# TE2015_Expansion_Board.net
KiCad netlist of a schematic drawn in EAGLE
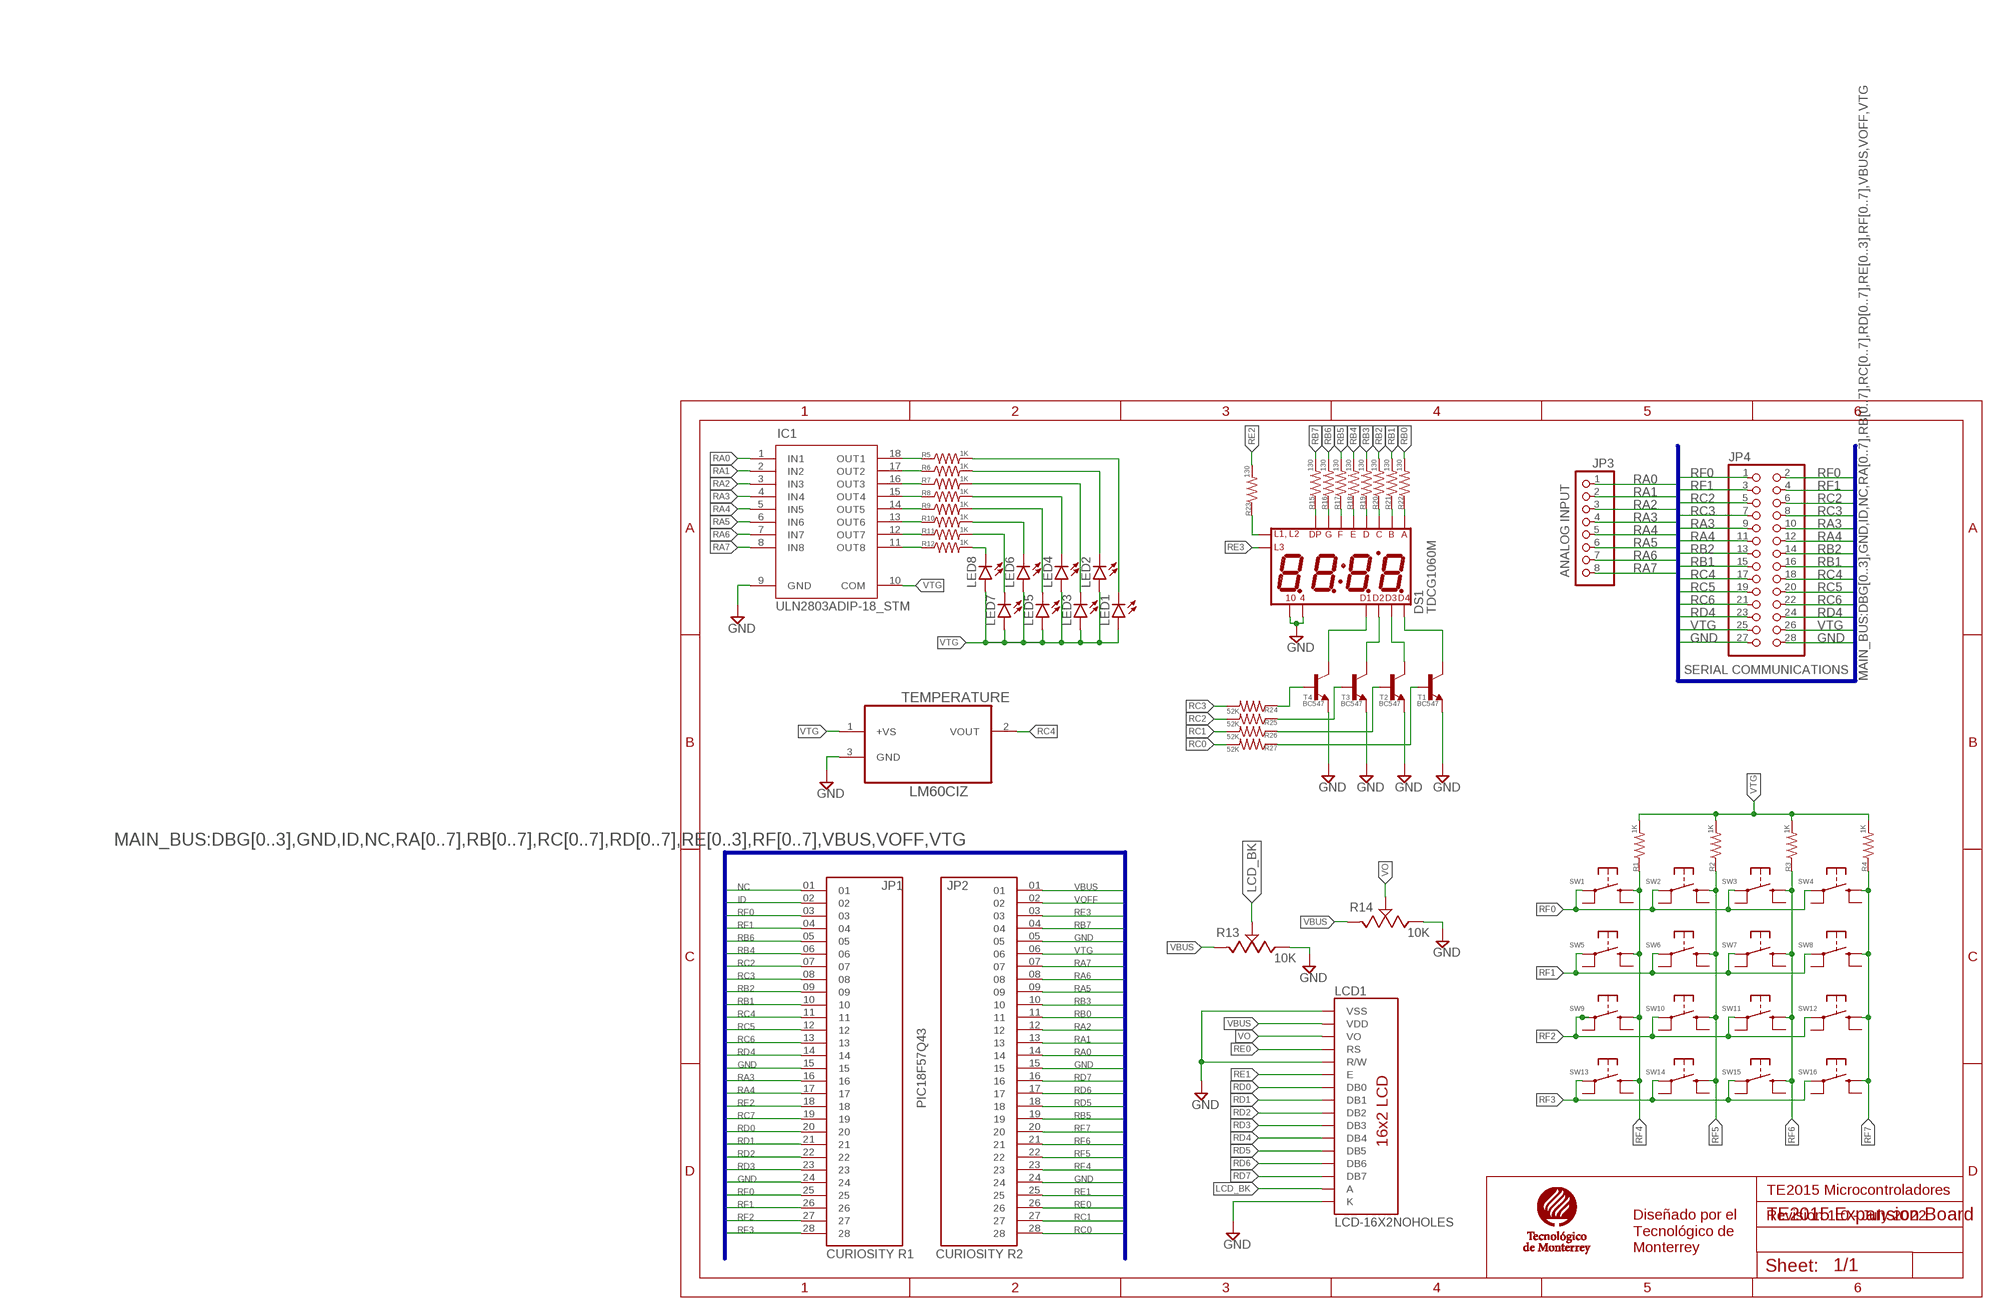
[diagram p0: schematic, sheet 1]

(export (version "E")
  (design (tool "Eeschema 10.0.6"))
  (components
    (comp (ref "DS1")
      (value "TDCG1060M")
      (footprint "eagle-import:DISPLAY_TDCG1060M")
      (fields (field (name "DIGI-KEY_PART_NUMBER") "TDCG1060M-ND") (field (name "MF") "Vishay"))
      (libsource (lib "eagle-import") (part "TDCG1060M"))
    )
    (comp (ref "IC1")
      (value "ULN2803ADIP-18_STM")
      (footprint "eagle-import:DIP-18_STM")
      (fields
        (field (name "MANUFACTURER_PART_NUMBER") "ULN2803A")
        (field (name "COPYRIGHT") "Copyright (C) 2022 Ultra Librarian. All rights reserved.")
      )
      (libsource (lib "eagle-import") (part "ULN2803ADIP-18_STM"))
    )
    (comp (ref "JP1")
      (value "CURIOSITY R1")
      (footprint "eagle-import:SAMTEC_SS-128-T-2")
      (fields
        (field (name "DIGI-KEY_PART_NUMBER") "SAM1117-28-ND")
        (field (name "MF") "Samtec")
        (field (name "MP") "SS-128-T-2")
      )
      (libsource (lib "eagle-import") (part "SS-128-T-2"))
    )
    (comp (ref "JP2")
      (value "CURIOSITY R2")
      (footprint "eagle-import:SAMTEC_SS-128-T-2")
      (fields
        (field (name "DIGI-KEY_PART_NUMBER") "SAM1117-28-ND")
        (field (name "MF") "Samtec")
        (field (name "MP") "SS-128-T-2")
      )
      (libsource (lib "eagle-import") (part "SS-128-T-2"))
    )
    (comp (ref "JP3")
      (value "ANALOG INPUT")
      (footprint "eagle-import:1X08-BIG")
      (libsource (lib "eagle-import") (part "PINHD-1X8BIG"))
    )
    (comp (ref "JP4")
      (value "SERIAL COMMUNICATIONS")
      (footprint "eagle-import:2X14-BIG")
      (libsource (lib "eagle-import") (part "PINHD-2X14-CB"))
    )
    (comp (ref "LCD1")
      (value "LCD-16X2NOHOLES")
      (footprint "eagle-import:LCD-16X2_NOHOLESNOSILK")
      (libsource (lib "eagle-import") (part "LCD-16X2NOHOLES"))
    )
    (comp (ref "LED1")
      (value "LED3MM")
      (footprint "eagle-import:LED3MM")
      (libsource (lib "eagle-import") (part "LED3MM"))
    )
    (comp (ref "LED2")
      (value "LED3MM")
      (footprint "eagle-import:LED3MM")
      (libsource (lib "eagle-import") (part "LED3MM"))
    )
    (comp (ref "LED3")
      (value "LED3MM")
      (footprint "eagle-import:LED3MM")
      (libsource (lib "eagle-import") (part "LED3MM"))
    )
    (comp (ref "LED4")
      (value "LED3MM")
      (footprint "eagle-import:LED3MM")
      (libsource (lib "eagle-import") (part "LED3MM"))
    )
    (comp (ref "LED5")
      (value "LED3MM")
      (footprint "eagle-import:LED3MM")
      (libsource (lib "eagle-import") (part "LED3MM"))
    )
    (comp (ref "LED6")
      (value "LED3MM")
      (footprint "eagle-import:LED3MM")
      (libsource (lib "eagle-import") (part "LED3MM"))
    )
    (comp (ref "LED7")
      (value "LED3MM")
      (footprint "eagle-import:LED3MM")
      (libsource (lib "eagle-import") (part "LED3MM"))
    )
    (comp (ref "LED8")
      (value "LED3MM")
      (footprint "eagle-import:LED3MM")
      (libsource (lib "eagle-import") (part "LED3MM"))
    )
    (comp (ref "R1")
      (value "1K")
      (footprint "eagle-import:0207_10")
      (libsource (lib "eagle-import") (part "R-US"))
    )
    (comp (ref "R2")
      (value "1K")
      (footprint "eagle-import:0207_10")
      (libsource (lib "eagle-import") (part "R-US"))
    )
    (comp (ref "R3")
      (value "1K")
      (footprint "eagle-import:0207_10")
      (libsource (lib "eagle-import") (part "R-US"))
    )
    (comp (ref "R4")
      (value "1K")
      (footprint "eagle-import:0207_10")
      (libsource (lib "eagle-import") (part "R-US"))
    )
    (comp (ref "R5")
      (value "1K")
      (footprint "eagle-import:0207_10")
      (libsource (lib "eagle-import") (part "R-US"))
    )
    (comp (ref "R6")
      (value "1K")
      (footprint "eagle-import:0207_10")
      (libsource (lib "eagle-import") (part "R-US"))
    )
    (comp (ref "R7")
      (value "1K")
      (footprint "eagle-import:0207_10")
      (libsource (lib "eagle-import") (part "R-US"))
    )
    (comp (ref "R8")
      (value "1K")
      (footprint "eagle-import:0207_10")
      (libsource (lib "eagle-import") (part "R-US"))
    )
    (comp (ref "R9")
      (value "1K")
      (footprint "eagle-import:0207_10")
      (libsource (lib "eagle-import") (part "R-US"))
    )
    (comp (ref "R10")
      (value "1K")
      (footprint "eagle-import:0207_10")
      (libsource (lib "eagle-import") (part "R-US"))
    )
    (comp (ref "R11")
      (value "1K")
      (footprint "eagle-import:0207_10")
      (libsource (lib "eagle-import") (part "R-US"))
    )
    (comp (ref "R12")
      (value "1K")
      (footprint "eagle-import:0207_10")
      (libsource (lib "eagle-import") (part "R-US"))
    )
    (comp (ref "R13")
      (value "10K")
      (footprint "eagle-import:3362P-1-103LF")
      (fields
        (field (name "MANUFACTURER") "Bourns Inc.")
        (field (name "MPN") "3362P-1-103LF")
        (field (name "CREATED_PN") "PCBLayout.com")
      )
      (libsource (lib "eagle-import") (part "3362P-1-103LF"))
    )
    (comp (ref "R14")
      (value "10K")
      (footprint "eagle-import:3362P-1-103LF")
      (fields
        (field (name "MANUFACTURER") "Bourns Inc.")
        (field (name "MPN") "3362P-1-103LF")
        (field (name "CREATED_PN") "PCBLayout.com")
      )
      (libsource (lib "eagle-import") (part "3362P-1-103LF"))
    )
    (comp (ref "R15")
      (value "130")
      (footprint "eagle-import:0207_10")
      (libsource (lib "eagle-import") (part "R-US"))
    )
    (comp (ref "R16")
      (value "130")
      (footprint "eagle-import:0207_10")
      (libsource (lib "eagle-import") (part "R-US"))
    )
    (comp (ref "R17")
      (value "130")
      (footprint "eagle-import:0207_10")
      (libsource (lib "eagle-import") (part "R-US"))
    )
    (comp (ref "R18")
      (value "130")
      (footprint "eagle-import:0207_10")
      (libsource (lib "eagle-import") (part "R-US"))
    )
    (comp (ref "R19")
      (value "130")
      (footprint "eagle-import:0207_10")
      (libsource (lib "eagle-import") (part "R-US"))
    )
    (comp (ref "R20")
      (value "130")
      (footprint "eagle-import:0207_10")
      (libsource (lib "eagle-import") (part "R-US"))
    )
    (comp (ref "R21")
      (value "130")
      (footprint "eagle-import:0207_10")
      (libsource (lib "eagle-import") (part "R-US"))
    )
    (comp (ref "R22")
      (value "130")
      (footprint "eagle-import:0207_10")
      (libsource (lib "eagle-import") (part "R-US"))
    )
    (comp (ref "R23")
      (value "130")
      (footprint "eagle-import:0207_10")
      (libsource (lib "eagle-import") (part "R-US"))
    )
    (comp (ref "R24")
      (value "52K")
      (footprint "eagle-import:0207_10")
      (libsource (lib "eagle-import") (part "R-US"))
    )
    (comp (ref "R25")
      (value "52K")
      (footprint "eagle-import:0207_10")
      (libsource (lib "eagle-import") (part "R-US"))
    )
    (comp (ref "R26")
      (value "52K")
      (footprint "eagle-import:0207_10")
      (libsource (lib "eagle-import") (part "R-US"))
    )
    (comp (ref "R27")
      (value "52K")
      (footprint "eagle-import:0207_10")
      (libsource (lib "eagle-import") (part "R-US"))
    )
    (comp (ref "SW1")
      (value "1825910-2")
      (footprint "eagle-import:TE_1825910-2")
      (fields (field (name "MF") "TE Connectivity"))
      (libsource (lib "eagle-import") (part "1825910-2"))
    )
    (comp (ref "SW2")
      (value "1825910-2")
      (footprint "eagle-import:TE_1825910-2")
      (fields (field (name "MF") "TE Connectivity"))
      (libsource (lib "eagle-import") (part "1825910-2"))
    )
    (comp (ref "SW3")
      (value "1825910-2")
      (footprint "eagle-import:TE_1825910-2")
      (fields (field (name "MF") "TE Connectivity"))
      (libsource (lib "eagle-import") (part "1825910-2"))
    )
    (comp (ref "SW4")
      (value "1825910-2")
      (footprint "eagle-import:TE_1825910-2")
      (fields (field (name "MF") "TE Connectivity"))
      (libsource (lib "eagle-import") (part "1825910-2"))
    )
    (comp (ref "SW5")
      (value "1825910-2")
      (footprint "eagle-import:TE_1825910-2")
      (fields (field (name "MF") "TE Connectivity"))
      (libsource (lib "eagle-import") (part "1825910-2"))
    )
    (comp (ref "SW6")
      (value "1825910-2")
      (footprint "eagle-import:TE_1825910-2")
      (fields (field (name "MF") "TE Connectivity"))
      (libsource (lib "eagle-import") (part "1825910-2"))
    )
    (comp (ref "SW7")
      (value "1825910-2")
      (footprint "eagle-import:TE_1825910-2")
      (fields (field (name "MF") "TE Connectivity"))
      (libsource (lib "eagle-import") (part "1825910-2"))
    )
    (comp (ref "SW8")
      (value "1825910-2")
      (footprint "eagle-import:TE_1825910-2")
      (fields (field (name "MF") "TE Connectivity"))
      (libsource (lib "eagle-import") (part "1825910-2"))
    )
    (comp (ref "SW9")
      (value "1825910-2")
      (footprint "eagle-import:TE_1825910-2")
      (fields (field (name "MF") "TE Connectivity"))
      (libsource (lib "eagle-import") (part "1825910-2"))
    )
    (comp (ref "SW10")
      (value "1825910-2")
      (footprint "eagle-import:TE_1825910-2")
      (fields (field (name "MF") "TE Connectivity"))
      (libsource (lib "eagle-import") (part "1825910-2"))
    )
    (comp (ref "SW11")
      (value "1825910-2")
      (footprint "eagle-import:TE_1825910-2")
      (fields (field (name "MF") "TE Connectivity"))
      (libsource (lib "eagle-import") (part "1825910-2"))
    )
    (comp (ref "SW12")
      (value "1825910-2")
      (footprint "eagle-import:TE_1825910-2")
      (fields (field (name "MF") "TE Connectivity"))
      (libsource (lib "eagle-import") (part "1825910-2"))
    )
    (comp (ref "SW13")
      (value "1825910-2")
      (footprint "eagle-import:TE_1825910-2")
      (fields (field (name "MF") "TE Connectivity"))
      (libsource (lib "eagle-import") (part "1825910-2"))
    )
    (comp (ref "SW14")
      (value "1825910-2")
      (footprint "eagle-import:TE_1825910-2")
      (fields (field (name "MF") "TE Connectivity"))
      (libsource (lib "eagle-import") (part "1825910-2"))
    )
    (comp (ref "SW15")
      (value "1825910-2")
      (footprint "eagle-import:TE_1825910-2")
      (fields (field (name "MF") "TE Connectivity"))
      (libsource (lib "eagle-import") (part "1825910-2"))
    )
    (comp (ref "SW16")
      (value "1825910-2")
      (footprint "eagle-import:TE_1825910-2")
      (fields (field (name "MF") "TE Connectivity"))
      (libsource (lib "eagle-import") (part "1825910-2"))
    )
    (comp (ref "T1")
      (value "BC547")
      (footprint "eagle-import:TO92")
      (libsource (lib "eagle-import") (part "BC547"))
    )
    (comp (ref "T2")
      (value "BC547")
      (footprint "eagle-import:TO92")
      (libsource (lib "eagle-import") (part "BC547"))
    )
    (comp (ref "T3")
      (value "BC547")
      (footprint "eagle-import:TO92")
      (libsource (lib "eagle-import") (part "BC547"))
    )
    (comp (ref "T4")
      (value "BC547")
      (footprint "eagle-import:TO92")
      (libsource (lib "eagle-import") (part "BC547"))
    )
    (comp (ref "TEC1")
      (value "TEC_LOGO")
      (footprint "eagle-import:TEC_LOGO")
      (libsource (lib "eagle-import") (part "TEC_LOGO"))
    )
    (comp (ref "TEMPERATURE")
      (value "LM60CIZ")
      (footprint "eagle-import:TO92_")
      (libsource (lib "eagle-import") (part "LM60CIZ"))
    )
  )
  (nets
    (net (code "1") (name "/ID") (class "Default")
      (node (ref "JP1") (pin "02") (pinfunction "02_02") (pintype "passive"))
    )
    (net (code "2") (name "/NC") (class "Default")
      (node (ref "JP1") (pin "01") (pinfunction "01_01") (pintype "passive"))
    )
    (net (code "3") (name "/RC5") (class "Default")
      (node (ref "JP1") (pin "12") (pinfunction "12_12") (pintype "passive"))
      (node (ref "JP4") (pin "19") (pinfunction "19_19") (pintype "passive"))
      (node (ref "JP4") (pin "20") (pinfunction "20_20") (pintype "passive"))
    )
    (net (code "4") (name "/RC6") (class "Default")
      (node (ref "JP1") (pin "13") (pinfunction "13_13") (pintype "passive"))
      (node (ref "JP4") (pin "21") (pinfunction "21_21") (pintype "passive"))
      (node (ref "JP4") (pin "22") (pinfunction "22_22") (pintype "passive"))
    )
    (net (code "5") (name "/RC7") (class "Default")
      (node (ref "JP1") (pin "19") (pinfunction "19_19") (pintype "passive"))
    )
    (net (code "6") (name "/VOFF") (class "Default")
      (node (ref "JP2") (pin "02") (pinfunction "02_02") (pintype "passive"))
    )
    (net (code "8") (name "GND") (class "Default")
      (node (ref "DS1") (pin "10") (pinfunction "10_10") (pintype "passive"))
      (node (ref "DS1") (pin "4") (pinfunction "4_4") (pintype "passive"))
      (node (ref "IC1") (pin "9") (pinfunction "GND_9") (pintype "power_in"))
      (node (ref "JP1") (pin "15") (pinfunction "15_15") (pintype "passive"))
      (node (ref "JP1") (pin "24") (pinfunction "24_24") (pintype "passive"))
      (node (ref "JP2") (pin "05") (pinfunction "05_05") (pintype "passive"))
      (node (ref "JP2") (pin "15") (pinfunction "15_15") (pintype "passive"))
      (node (ref "JP2") (pin "24") (pinfunction "24_24") (pintype "passive"))
      (node (ref "JP4") (pin "27") (pinfunction "27_27") (pintype "passive"))
      (node (ref "JP4") (pin "28") (pinfunction "28_28") (pintype "passive"))
      (node (ref "LCD1") (pin "1") (pinfunction "VSS_1") (pintype "power_in"))
      (node (ref "LCD1") (pin "16") (pinfunction "K_16") (pintype "power_in"))
      (node (ref "LCD1") (pin "5") (pinfunction "R/W_5") (pintype "input"))
      (node (ref "R13") (pin "3") (pinfunction "3_3") (pintype "passive"))
      (node (ref "R14") (pin "3") (pinfunction "3_3") (pintype "passive"))
      (node (ref "T1") (pin "1") (pinfunction "E_1") (pintype "passive"))
      (node (ref "T2") (pin "1") (pinfunction "E_1") (pintype "passive"))
      (node (ref "T3") (pin "1") (pinfunction "E_1") (pintype "passive"))
      (node (ref "T4") (pin "1") (pinfunction "E_1") (pintype "passive"))
      (node (ref "TEMPERATURE") (pin "3") (pinfunction "GND_3") (pintype "passive"))
    )
    (net (code "9") (name "LCD_BK") (class "Default")
      (node (ref "LCD1") (pin "15") (pinfunction "A_15") (pintype "power_in"))
      (node (ref "R13") (pin "2") (pinfunction "2_2") (pintype "passive"))
    )
    (net (code "10") (name "Net-(DS1-A)") (class "Default")
      (node (ref "DS1") (pin "14") (pinfunction "A_14") (pintype "passive"))
      (node (ref "R22") (pin "1") (pinfunction "1_1") (pintype "passive"))
    )
    (net (code "11") (name "Net-(DS1-B)") (class "Default")
      (node (ref "DS1") (pin "16") (pinfunction "B_16") (pintype "passive"))
      (node (ref "R21") (pin "1") (pinfunction "1_1") (pintype "passive"))
    )
    (net (code "12") (name "Net-(DS1-C)") (class "Default")
      (node (ref "DS1") (pin "13") (pinfunction "C_13") (pintype "passive"))
      (node (ref "R20") (pin "1") (pinfunction "1_1") (pintype "passive"))
    )
    (net (code "13") (name "Net-(DS1-D)") (class "Default")
      (node (ref "DS1") (pin "3") (pinfunction "D_3") (pintype "passive"))
      (node (ref "R19") (pin "1") (pinfunction "1_1") (pintype "passive"))
    )
    (net (code "14") (name "Net-(DS1-DIG1)") (class "Default")
      (node (ref "DS1") (pin "1") (pinfunction "DIG1_1") (pintype "passive"))
      (node (ref "T4") (pin "3") (pinfunction "C_3") (pintype "passive"))
    )
    (net (code "15") (name "Net-(DS1-DIG2)") (class "Default")
      (node (ref "DS1") (pin "2") (pinfunction "DIG2_2") (pintype "passive"))
      (node (ref "T3") (pin "3") (pinfunction "C_3") (pintype "passive"))
    )
    (net (code "16") (name "Net-(DS1-DIG3)") (class "Default")
      (node (ref "DS1") (pin "6") (pinfunction "DIG3_6") (pintype "passive"))
      (node (ref "T2") (pin "3") (pinfunction "C_3") (pintype "passive"))
    )
    (net (code "17") (name "Net-(DS1-DIG4)") (class "Default")
      (node (ref "DS1") (pin "8") (pinfunction "DIG4_8") (pintype "passive"))
      (node (ref "T1") (pin "3") (pinfunction "C_3") (pintype "passive"))
    )
    (net (code "18") (name "Net-(DS1-DP)") (class "Default")
      (node (ref "DS1") (pin "7") (pinfunction "DP_7") (pintype "passive"))
      (node (ref "R15") (pin "1") (pinfunction "1_1") (pintype "passive"))
    )
    (net (code "19") (name "Net-(DS1-E)") (class "Default")
      (node (ref "DS1") (pin "5") (pinfunction "E_5") (pintype "passive"))
      (node (ref "R18") (pin "1") (pinfunction "1_1") (pintype "passive"))
    )
    (net (code "20") (name "Net-(DS1-F)") (class "Default")
      (node (ref "DS1") (pin "11") (pinfunction "F_11") (pintype "passive"))
      (node (ref "R17") (pin "1") (pinfunction "1_1") (pintype "passive"))
    )
    (net (code "21") (name "Net-(DS1-G)") (class "Default")
      (node (ref "DS1") (pin "15") (pinfunction "G_15") (pintype "passive"))
      (node (ref "R16") (pin "1") (pinfunction "1_1") (pintype "passive"))
    )
    (net (code "22") (name "Net-(DS1-L1_L2)") (class "Default")
      (node (ref "DS1") (pin "12") (pinfunction "L1_L2_12") (pintype "passive"))
      (node (ref "R23") (pin "1") (pinfunction "1_1") (pintype "passive"))
    )
    (net (code "23") (name "Net-(IC1-OUT1)") (class "Default")
      (node (ref "IC1") (pin "18") (pinfunction "OUT1_18") (pintype "passive"))
      (node (ref "R5") (pin "1") (pinfunction "1_1") (pintype "passive"))
    )
    (net (code "24") (name "Net-(IC1-OUT2)") (class "Default")
      (node (ref "IC1") (pin "17") (pinfunction "OUT2_17") (pintype "passive"))
      (node (ref "R6") (pin "1") (pinfunction "1_1") (pintype "passive"))
    )
    (net (code "25") (name "Net-(IC1-OUT3)") (class "Default")
      (node (ref "IC1") (pin "16") (pinfunction "OUT3_16") (pintype "passive"))
      (node (ref "R7") (pin "1") (pinfunction "1_1") (pintype "passive"))
    )
    (net (code "26") (name "Net-(IC1-OUT4)") (class "Default")
      (node (ref "IC1") (pin "15") (pinfunction "OUT4_15") (pintype "passive"))
      (node (ref "R8") (pin "1") (pinfunction "1_1") (pintype "passive"))
    )
    (net (code "27") (name "Net-(IC1-OUT5)") (class "Default")
      (node (ref "IC1") (pin "14") (pinfunction "OUT5_14") (pintype "passive"))
      (node (ref "R9") (pin "1") (pinfunction "1_1") (pintype "passive"))
    )
    (net (code "28") (name "Net-(IC1-OUT6)") (class "Default")
      (node (ref "IC1") (pin "13") (pinfunction "OUT6_13") (pintype "passive"))
      (node (ref "R10") (pin "1") (pinfunction "1_1") (pintype "passive"))
    )
    (net (code "29") (name "Net-(IC1-OUT7)") (class "Default")
      (node (ref "IC1") (pin "12") (pinfunction "OUT7_12") (pintype "passive"))
      (node (ref "R11") (pin "1") (pinfunction "1_1") (pintype "passive"))
    )
    (net (code "30") (name "Net-(IC1-OUT8)") (class "Default")
      (node (ref "IC1") (pin "11") (pinfunction "OUT8_11") (pintype "passive"))
      (node (ref "R12") (pin "1") (pinfunction "1_1") (pintype "passive"))
    )
    (net (code "31") (name "Net-(LED1-C)") (class "Default")
      (node (ref "LED1") (pin "K") (pinfunction "C_K") (pintype "passive"))
      (node (ref "R5") (pin "2") (pinfunction "2_2") (pintype "passive"))
    )
    (net (code "32") (name "Net-(LED2-C)") (class "Default")
      (node (ref "LED2") (pin "K") (pinfunction "C_K") (pintype "passive"))
      (node (ref "R6") (pin "2") (pinfunction "2_2") (pintype "passive"))
    )
    (net (code "33") (name "Net-(LED3-C)") (class "Default")
      (node (ref "LED3") (pin "K") (pinfunction "C_K") (pintype "passive"))
      (node (ref "R7") (pin "2") (pinfunction "2_2") (pintype "passive"))
    )
    (net (code "34") (name "Net-(LED4-C)") (class "Default")
      (node (ref "LED4") (pin "K") (pinfunction "C_K") (pintype "passive"))
      (node (ref "R8") (pin "2") (pinfunction "2_2") (pintype "passive"))
    )
    (net (code "35") (name "Net-(LED5-C)") (class "Default")
      (node (ref "LED5") (pin "K") (pinfunction "C_K") (pintype "passive"))
      (node (ref "R9") (pin "2") (pinfunction "2_2") (pintype "passive"))
    )
    (net (code "36") (name "Net-(LED6-C)") (class "Default")
      (node (ref "LED6") (pin "K") (pinfunction "C_K") (pintype "passive"))
      (node (ref "R10") (pin "2") (pinfunction "2_2") (pintype "passive"))
    )
    (net (code "37") (name "Net-(LED7-C)") (class "Default")
      (node (ref "LED7") (pin "K") (pinfunction "C_K") (pintype "passive"))
      (node (ref "R11") (pin "2") (pinfunction "2_2") (pintype "passive"))
    )
    (net (code "38") (name "Net-(LED8-C)") (class "Default")
      (node (ref "LED8") (pin "K") (pinfunction "C_K") (pintype "passive"))
      (node (ref "R12") (pin "2") (pinfunction "2_2") (pintype "passive"))
    )
    (net (code "39") (name "Net-(T1-B)") (class "Default")
      (node (ref "R27") (pin "1") (pinfunction "1_1") (pintype "passive"))
      (node (ref "T1") (pin "2") (pinfunction "B_2") (pintype "passive"))
    )
    (net (code "40") (name "Net-(T2-B)") (class "Default")
      (node (ref "R26") (pin "1") (pinfunction "1_1") (pintype "passive"))
      (node (ref "T2") (pin "2") (pinfunction "B_2") (pintype "passive"))
    )
    (net (code "41") (name "Net-(T3-B)") (class "Default")
      (node (ref "R25") (pin "1") (pinfunction "1_1") (pintype "passive"))
      (node (ref "T3") (pin "2") (pinfunction "B_2") (pintype "passive"))
    )
    (net (code "42") (name "Net-(T4-B)") (class "Default")
      (node (ref "R24") (pin "1") (pinfunction "1_1") (pintype "passive"))
      (node (ref "T4") (pin "2") (pinfunction "B_2") (pintype "passive"))
    )
    (net (code "43") (name "RA0") (class "Default")
      (node (ref "IC1") (pin "1") (pinfunction "IN1_1") (pintype "input"))
      (node (ref "JP2") (pin "14") (pinfunction "14_14") (pintype "passive"))
      (node (ref "JP3") (pin "1") (pinfunction "1_1") (pintype "passive"))
    )
    (net (code "44") (name "RA1") (class "Default")
      (node (ref "IC1") (pin "2") (pinfunction "IN2_2") (pintype "input"))
      (node (ref "JP2") (pin "13") (pinfunction "13_13") (pintype "passive"))
      (node (ref "JP3") (pin "2") (pinfunction "2_2") (pintype "passive"))
    )
    (net (code "45") (name "RA2") (class "Default")
      (node (ref "IC1") (pin "3") (pinfunction "IN3_3") (pintype "input"))
      (node (ref "JP2") (pin "12") (pinfunction "12_12") (pintype "passive"))
      (node (ref "JP3") (pin "3") (pinfunction "3_3") (pintype "passive"))
    )
    (net (code "46") (name "RA3") (class "Default")
      (node (ref "IC1") (pin "4") (pinfunction "IN4_4") (pintype "input"))
      (node (ref "JP1") (pin "16") (pinfunction "16_16") (pintype "passive"))
      (node (ref "JP3") (pin "4") (pinfunction "4_4") (pintype "passive"))
      (node (ref "JP4") (pin "10") (pinfunction "10_10") (pintype "passive"))
      (node (ref "JP4") (pin "9") (pinfunction "9_9") (pintype "passive"))
    )
    (net (code "47") (name "RA4") (class "Default")
      (node (ref "IC1") (pin "5") (pinfunction "IN5_5") (pintype "input"))
      (node (ref "JP1") (pin "17") (pinfunction "17_17") (pintype "passive"))
      (node (ref "JP3") (pin "5") (pinfunction "5_5") (pintype "passive"))
      (node (ref "JP4") (pin "11") (pinfunction "11_11") (pintype "passive"))
      (node (ref "JP4") (pin "12") (pinfunction "12_12") (pintype "passive"))
    )
    (net (code "48") (name "RA5") (class "Default")
      (node (ref "IC1") (pin "6") (pinfunction "IN6_6") (pintype "input"))
      (node (ref "JP2") (pin "09") (pinfunction "09_09") (pintype "passive"))
      (node (ref "JP3") (pin "6") (pinfunction "6_6") (pintype "passive"))
    )
    (net (code "49") (name "RA6") (class "Default")
      (node (ref "IC1") (pin "7") (pinfunction "IN7_7") (pintype "input"))
      (node (ref "JP2") (pin "08") (pinfunction "08_08") (pintype "passive"))
      (node (ref "JP3") (pin "7") (pinfunction "7_7") (pintype "passive"))
    )
    (net (code "50") (name "RA7") (class "Default")
      (node (ref "IC1") (pin "8") (pinfunction "IN8_8") (pintype "input"))
      (node (ref "JP2") (pin "07") (pinfunction "07_07") (pintype "passive"))
      (node (ref "JP3") (pin "8") (pinfunction "8_8") (pintype "passive"))
    )
    (net (code "51") (name "RB0") (class "Default")
      (node (ref "JP2") (pin "11") (pinfunction "11_11") (pintype "passive"))
      (node (ref "R22") (pin "2") (pinfunction "2_2") (pintype "passive"))
    )
    (net (code "52") (name "RB1") (class "Default")
      (node (ref "JP1") (pin "10") (pinfunction "10_10") (pintype "passive"))
      (node (ref "JP4") (pin "15") (pinfunction "15_15") (pintype "passive"))
      (node (ref "JP4") (pin "16") (pinfunction "16_16") (pintype "passive"))
      (node (ref "R21") (pin "2") (pinfunction "2_2") (pintype "passive"))
    )
    (net (code "53") (name "RB2") (class "Default")
      (node (ref "JP1") (pin "09") (pinfunction "09_09") (pintype "passive"))
      (node (ref "JP4") (pin "13") (pinfunction "13_13") (pintype "passive"))
      (node (ref "JP4") (pin "14") (pinfunction "14_14") (pintype "passive"))
      (node (ref "R20") (pin "2") (pinfunction "2_2") (pintype "passive"))
    )
    (net (code "54") (name "RB3") (class "Default")
      (node (ref "JP2") (pin "10") (pinfunction "10_10") (pintype "passive"))
      (node (ref "R19") (pin "2") (pinfunction "2_2") (pintype "passive"))
    )
    (net (code "55") (name "RB4") (class "Default")
      (node (ref "JP1") (pin "06") (pinfunction "06_06") (pintype "passive"))
      (node (ref "R18") (pin "2") (pinfunction "2_2") (pintype "passive"))
    )
    (net (code "56") (name "RB5") (class "Default")
      (node (ref "JP2") (pin "19") (pinfunction "19_19") (pintype "passive"))
      (node (ref "R17") (pin "2") (pinfunction "2_2") (pintype "passive"))
    )
    (net (code "57") (name "RB6") (class "Default")
      (node (ref "JP1") (pin "05") (pinfunction "05_05") (pintype "passive"))
      (node (ref "R16") (pin "2") (pinfunction "2_2") (pintype "passive"))
    )
    (net (code "58") (name "RB7") (class "Default")
      (node (ref "JP2") (pin "04") (pinfunction "04_04") (pintype "passive"))
      (node (ref "R15") (pin "2") (pinfunction "2_2") (pintype "passive"))
    )
    (net (code "59") (name "RC0") (class "Default")
      (node (ref "JP2") (pin "28") (pinfunction "28_28") (pintype "passive"))
      (node (ref "R27") (pin "2") (pinfunction "2_2") (pintype "passive"))
    )
    (net (code "60") (name "RC1") (class "Default")
      (node (ref "JP2") (pin "27") (pinfunction "27_27") (pintype "passive"))
      (node (ref "R26") (pin "2") (pinfunction "2_2") (pintype "passive"))
    )
    (net (code "61") (name "RC2") (class "Default")
      (node (ref "JP1") (pin "07") (pinfunction "07_07") (pintype "passive"))
      (node (ref "JP4") (pin "5") (pinfunction "5_5") (pintype "passive"))
      (node (ref "JP4") (pin "6") (pinfunction "6_6") (pintype "passive"))
      (node (ref "R25") (pin "2") (pinfunction "2_2") (pintype "passive"))
    )
    (net (code "62") (name "RC3") (class "Default")
      (node (ref "JP1") (pin "08") (pinfunction "08_08") (pintype "passive"))
      (node (ref "JP4") (pin "7") (pinfunction "7_7") (pintype "passive"))
      (node (ref "JP4") (pin "8") (pinfunction "8_8") (pintype "passive"))
      (node (ref "R24") (pin "2") (pinfunction "2_2") (pintype "passive"))
    )
    (net (code "63") (name "RC4") (class "Default")
      (node (ref "JP1") (pin "11") (pinfunction "11_11") (pintype "passive"))
      (node (ref "JP4") (pin "17") (pinfunction "17_17") (pintype "passive"))
      (node (ref "JP4") (pin "18") (pinfunction "18_18") (pintype "passive"))
      (node (ref "TEMPERATURE") (pin "2") (pinfunction "VOUT_2") (pintype "output"))
    )
    (net (code "64") (name "RD0") (class "Default")
      (node (ref "JP1") (pin "20") (pinfunction "20_20") (pintype "passive"))
      (node (ref "LCD1") (pin "7") (pinfunction "DB0_7") (pintype "bidirectional"))
    )
    (net (code "65") (name "RD1") (class "Default")
      (node (ref "JP1") (pin "21") (pinfunction "21_21") (pintype "passive"))
      (node (ref "LCD1") (pin "8") (pinfunction "DB1_8") (pintype "bidirectional"))
    )
    (net (code "66") (name "RD2") (class "Default")
      (node (ref "JP1") (pin "22") (pinfunction "22_22") (pintype "passive"))
      (node (ref "LCD1") (pin "9") (pinfunction "DB2_9") (pintype "bidirectional"))
    )
    (net (code "67") (name "RD3") (class "Default")
      (node (ref "JP1") (pin "23") (pinfunction "23_23") (pintype "passive"))
      (node (ref "LCD1") (pin "10") (pinfunction "DB3_10") (pintype "bidirectional"))
    )
    (net (code "68") (name "RD4") (class "Default")
      (node (ref "JP1") (pin "14") (pinfunction "14_14") (pintype "passive"))
      (node (ref "JP4") (pin "23") (pinfunction "23_23") (pintype "passive"))
      (node (ref "JP4") (pin "24") (pinfunction "24_24") (pintype "passive"))
      (node (ref "LCD1") (pin "11") (pinfunction "DB4_11") (pintype "bidirectional"))
    )
    (net (code "69") (name "RD5") (class "Default")
      (node (ref "JP2") (pin "18") (pinfunction "18_18") (pintype "passive"))
      (node (ref "LCD1") (pin "12") (pinfunction "DB5_12") (pintype "bidirectional"))
    )
    (net (code "70") (name "RD6") (class "Default")
      (node (ref "JP2") (pin "17") (pinfunction "17_17") (pintype "passive"))
      (node (ref "LCD1") (pin "13") (pinfunction "DB6_13") (pintype "bidirectional"))
    )
    (net (code "71") (name "RD7") (class "Default")
      (node (ref "JP2") (pin "16") (pinfunction "16_16") (pintype "passive"))
      (node (ref "LCD1") (pin "14") (pinfunction "DB7_14") (pintype "bidirectional"))
    )
    (net (code "72") (name "RE0") (class "Default")
      (node (ref "JP2") (pin "26") (pinfunction "26_26") (pintype "passive"))
      (node (ref "LCD1") (pin "4") (pinfunction "RS_4") (pintype "input"))
    )
    (net (code "73") (name "RE1") (class "Default")
      (node (ref "JP2") (pin "25") (pinfunction "25_25") (pintype "passive"))
      (node (ref "LCD1") (pin "6") (pinfunction "E_6") (pintype "input"))
    )
    (net (code "74") (name "RE2") (class "Default")
      (node (ref "JP1") (pin "18") (pinfunction "18_18") (pintype "passive"))
      (node (ref "R23") (pin "2") (pinfunction "2_2") (pintype "passive"))
    )
    (net (code "75") (name "RE3") (class "Default")
      (node (ref "DS1") (pin "9") (pinfunction "L3_9") (pintype "passive"))
      (node (ref "JP2") (pin "03") (pinfunction "03_03") (pintype "passive"))
    )
    (net (code "76") (name "RF0") (class "Default")
      (node (ref "JP1") (pin "03") (pinfunction "03_03") (pintype "passive"))
      (node (ref "JP1") (pin "25") (pinfunction "25_25") (pintype "passive"))
      (node (ref "JP4") (pin "1") (pinfunction "1_1") (pintype "passive"))
      (node (ref "JP4") (pin "2") (pinfunction "2_2") (pintype "passive"))
      (node (ref "SW1") (pin "1") (pinfunction "P_1") (pintype "passive"))
      (node (ref "SW2") (pin "1") (pinfunction "P_1") (pintype "passive"))
      (node (ref "SW3") (pin "1") (pinfunction "P_1") (pintype "passive"))
      (node (ref "SW4") (pin "1") (pinfunction "P_1") (pintype "passive"))
    )
    (net (code "77") (name "RF1") (class "Default")
      (node (ref "JP1") (pin "04") (pinfunction "04_04") (pintype "passive"))
      (node (ref "JP1") (pin "26") (pinfunction "26_26") (pintype "passive"))
      (node (ref "JP4") (pin "3") (pinfunction "3_3") (pintype "passive"))
      (node (ref "JP4") (pin "4") (pinfunction "4_4") (pintype "passive"))
      (node (ref "SW5") (pin "1") (pinfunction "P_1") (pintype "passive"))
      (node (ref "SW6") (pin "1") (pinfunction "P_1") (pintype "passive"))
      (node (ref "SW7") (pin "1") (pinfunction "P_1") (pintype "passive"))
      (node (ref "SW8") (pin "1") (pinfunction "P_1") (pintype "passive"))
    )
    (net (code "78") (name "RF2") (class "Default")
      (node (ref "JP1") (pin "27") (pinfunction "27_27") (pintype "passive"))
      (node (ref "SW10") (pin "1") (pinfunction "P_1") (pintype "passive"))
      (node (ref "SW11") (pin "1") (pinfunction "P_1") (pintype "passive"))
      (node (ref "SW12") (pin "1") (pinfunction "P_1") (pintype "passive"))
      (node (ref "SW9") (pin "1") (pinfunction "P_1") (pintype "passive"))
    )
    (net (code "79") (name "RF3") (class "Default")
      (node (ref "JP1") (pin "28") (pinfunction "28_28") (pintype "passive"))
      (node (ref "SW13") (pin "1") (pinfunction "P_1") (pintype "passive"))
      (node (ref "SW14") (pin "1") (pinfunction "P_1") (pintype "passive"))
      (node (ref "SW15") (pin "1") (pinfunction "P_1") (pintype "passive"))
      (node (ref "SW16") (pin "1") (pinfunction "P_1") (pintype "passive"))
    )
    (net (code "80") (name "RF4") (class "Default")
      (node (ref "JP2") (pin "23") (pinfunction "23_23") (pintype "passive"))
      (node (ref "R1") (pin "1") (pinfunction "1_1") (pintype "passive"))
      (node (ref "SW1") (pin "2") (pinfunction "S_2") (pintype "passive"))
      (node (ref "SW13") (pin "2") (pinfunction "S_2") (pintype "passive"))
      (node (ref "SW5") (pin "2") (pinfunction "S_2") (pintype "passive"))
      (node (ref "SW9") (pin "2") (pinfunction "S_2") (pintype "passive"))
    )
    (net (code "81") (name "RF5") (class "Default")
      (node (ref "JP2") (pin "22") (pinfunction "22_22") (pintype "passive"))
      (node (ref "R2") (pin "1") (pinfunction "1_1") (pintype "passive"))
      (node (ref "SW10") (pin "2") (pinfunction "S_2") (pintype "passive"))
      (node (ref "SW14") (pin "2") (pinfunction "S_2") (pintype "passive"))
      (node (ref "SW2") (pin "2") (pinfunction "S_2") (pintype "passive"))
      (node (ref "SW6") (pin "2") (pinfunction "S_2") (pintype "passive"))
    )
    (net (code "82") (name "RF6") (class "Default")
      (node (ref "JP2") (pin "21") (pinfunction "21_21") (pintype "passive"))
      (node (ref "R3") (pin "1") (pinfunction "1_1") (pintype "passive"))
      (node (ref "SW11") (pin "2") (pinfunction "S_2") (pintype "passive"))
      (node (ref "SW15") (pin "2") (pinfunction "S_2") (pintype "passive"))
      (node (ref "SW3") (pin "2") (pinfunction "S_2") (pintype "passive"))
      (node (ref "SW7") (pin "2") (pinfunction "S_2") (pintype "passive"))
    )
    (net (code "83") (name "RF7") (class "Default")
      (node (ref "JP2") (pin "20") (pinfunction "20_20") (pintype "passive"))
      (node (ref "R4") (pin "1") (pinfunction "1_1") (pintype "passive"))
      (node (ref "SW12") (pin "2") (pinfunction "S_2") (pintype "passive"))
      (node (ref "SW16") (pin "2") (pinfunction "S_2") (pintype "passive"))
      (node (ref "SW4") (pin "2") (pinfunction "S_2") (pintype "passive"))
      (node (ref "SW8") (pin "2") (pinfunction "S_2") (pintype "passive"))
    )
    (net (code "84") (name "VBUS") (class "Default")
      (node (ref "JP2") (pin "01") (pinfunction "01_01") (pintype "passive"))
      (node (ref "LCD1") (pin "2") (pinfunction "VDD_2") (pintype "power_in"))
      (node (ref "R13") (pin "1") (pinfunction "1_1") (pintype "passive"))
      (node (ref "R14") (pin "1") (pinfunction "1_1") (pintype "passive"))
    )
    (net (code "85") (name "VO") (class "Default")
      (node (ref "LCD1") (pin "3") (pinfunction "VO_3") (pintype "bidirectional"))
      (node (ref "R14") (pin "2") (pinfunction "2_2") (pintype "passive"))
    )
    (net (code "86") (name "VTG") (class "Default")
      (node (ref "IC1") (pin "10") (pinfunction "COM_10") (pintype "passive"))
      (node (ref "JP2") (pin "06") (pinfunction "06_06") (pintype "passive"))
      (node (ref "JP4") (pin "25") (pinfunction "25_25") (pintype "passive"))
      (node (ref "JP4") (pin "26") (pinfunction "26_26") (pintype "passive"))
      (node (ref "LED1") (pin "A") (pinfunction "A_A") (pintype "passive"))
      (node (ref "LED2") (pin "A") (pinfunction "A_A") (pintype "passive"))
      (node (ref "LED3") (pin "A") (pinfunction "A_A") (pintype "passive"))
      (node (ref "LED4") (pin "A") (pinfunction "A_A") (pintype "passive"))
      (node (ref "LED5") (pin "A") (pinfunction "A_A") (pintype "passive"))
      (node (ref "LED6") (pin "A") (pinfunction "A_A") (pintype "passive"))
      (node (ref "LED7") (pin "A") (pinfunction "A_A") (pintype "passive"))
      (node (ref "LED8") (pin "A") (pinfunction "A_A") (pintype "passive"))
      (node (ref "R1") (pin "2") (pinfunction "2_2") (pintype "passive"))
      (node (ref "R2") (pin "2") (pinfunction "2_2") (pintype "passive"))
      (node (ref "R3") (pin "2") (pinfunction "2_2") (pintype "passive"))
      (node (ref "R4") (pin "2") (pinfunction "2_2") (pintype "passive"))
      (node (ref "TEMPERATURE") (pin "1") (pinfunction "+VS_1") (pintype "power_in"))
    )
    (net (code "87") (name "unconnected-(SW1-P1-Pad3)") (class "Default")
      (node (ref "SW1") (pin "3") (pinfunction "P1_3") (pintype "passive"))
    )
    (net (code "88") (name "unconnected-(SW1-S1-Pad4)") (class "Default")
      (node (ref "SW1") (pin "4") (pinfunction "S1_4") (pintype "passive"))
    )
    (net (code "89") (name "unconnected-(SW2-P1-Pad3)") (class "Default")
      (node (ref "SW2") (pin "3") (pinfunction "P1_3") (pintype "passive"))
    )
    (net (code "90") (name "unconnected-(SW2-S1-Pad4)") (class "Default")
      (node (ref "SW2") (pin "4") (pinfunction "S1_4") (pintype "passive"))
    )
    (net (code "91") (name "unconnected-(SW3-P1-Pad3)") (class "Default")
      (node (ref "SW3") (pin "3") (pinfunction "P1_3") (pintype "passive"))
    )
    (net (code "92") (name "unconnected-(SW3-S1-Pad4)") (class "Default")
      (node (ref "SW3") (pin "4") (pinfunction "S1_4") (pintype "passive"))
    )
    (net (code "93") (name "unconnected-(SW4-P1-Pad3)") (class "Default")
      (node (ref "SW4") (pin "3") (pinfunction "P1_3") (pintype "passive"))
    )
    (net (code "94") (name "unconnected-(SW4-S1-Pad4)") (class "Default")
      (node (ref "SW4") (pin "4") (pinfunction "S1_4") (pintype "passive"))
    )
    (net (code "95") (name "unconnected-(SW5-P1-Pad3)") (class "Default")
      (node (ref "SW5") (pin "3") (pinfunction "P1_3") (pintype "passive"))
    )
    (net (code "96") (name "unconnected-(SW5-S1-Pad4)") (class "Default")
      (node (ref "SW5") (pin "4") (pinfunction "S1_4") (pintype "passive"))
    )
    (net (code "97") (name "unconnected-(SW6-P1-Pad3)") (class "Default")
      (node (ref "SW6") (pin "3") (pinfunction "P1_3") (pintype "passive"))
    )
    (net (code "98") (name "unconnected-(SW6-S1-Pad4)") (class "Default")
      (node (ref "SW6") (pin "4") (pinfunction "S1_4") (pintype "passive"))
    )
    (net (code "99") (name "unconnected-(SW7-P1-Pad3)") (class "Default")
      (node (ref "SW7") (pin "3") (pinfunction "P1_3") (pintype "passive"))
    )
    (net (code "100") (name "unconnected-(SW7-S1-Pad4)") (class "Default")
      (node (ref "SW7") (pin "4") (pinfunction "S1_4") (pintype "passive"))
    )
    (net (code "101") (name "unconnected-(SW8-P1-Pad3)") (class "Default")
      (node (ref "SW8") (pin "3") (pinfunction "P1_3") (pintype "passive"))
    )
    (net (code "102") (name "unconnected-(SW8-S1-Pad4)") (class "Default")
      (node (ref "SW8") (pin "4") (pinfunction "S1_4") (pintype "passive"))
    )
    (net (code "103") (name "unconnected-(SW9-P1-Pad3)") (class "Default")
      (node (ref "SW9") (pin "3") (pinfunction "P1_3") (pintype "passive"))
    )
    (net (code "104") (name "unconnected-(SW9-S1-Pad4)") (class "Default")
      (node (ref "SW9") (pin "4") (pinfunction "S1_4") (pintype "passive"))
    )
    (net (code "105") (name "unconnected-(SW10-P1-Pad3)") (class "Default")
      (node (ref "SW10") (pin "3") (pinfunction "P1_3") (pintype "passive"))
    )
    (net (code "106") (name "unconnected-(SW10-S1-Pad4)") (class "Default")
      (node (ref "SW10") (pin "4") (pinfunction "S1_4") (pintype "passive"))
    )
    (net (code "107") (name "unconnected-(SW11-P1-Pad3)") (class "Default")
      (node (ref "SW11") (pin "3") (pinfunction "P1_3") (pintype "passive"))
    )
    (net (code "108") (name "unconnected-(SW11-S1-Pad4)") (class "Default")
      (node (ref "SW11") (pin "4") (pinfunction "S1_4") (pintype "passive"))
    )
    (net (code "109") (name "unconnected-(SW12-P1-Pad3)") (class "Default")
      (node (ref "SW12") (pin "3") (pinfunction "P1_3") (pintype "passive"))
    )
    (net (code "110") (name "unconnected-(SW12-S1-Pad4)") (class "Default")
      (node (ref "SW12") (pin "4") (pinfunction "S1_4") (pintype "passive"))
    )
    (net (code "111") (name "unconnected-(SW13-P1-Pad3)") (class "Default")
      (node (ref "SW13") (pin "3") (pinfunction "P1_3") (pintype "passive"))
    )
    (net (code "112") (name "unconnected-(SW13-S1-Pad4)") (class "Default")
      (node (ref "SW13") (pin "4") (pinfunction "S1_4") (pintype "passive"))
    )
    (net (code "113") (name "unconnected-(SW14-P1-Pad3)") (class "Default")
      (node (ref "SW14") (pin "3") (pinfunction "P1_3") (pintype "passive"))
    )
    (net (code "114") (name "unconnected-(SW14-S1-Pad4)") (class "Default")
      (node (ref "SW14") (pin "4") (pinfunction "S1_4") (pintype "passive"))
    )
    (net (code "115") (name "unconnected-(SW15-P1-Pad3)") (class "Default")
      (node (ref "SW15") (pin "3") (pinfunction "P1_3") (pintype "passive"))
    )
    (net (code "116") (name "unconnected-(SW15-S1-Pad4)") (class "Default")
      (node (ref "SW15") (pin "4") (pinfunction "S1_4") (pintype "passive"))
    )
    (net (code "117") (name "unconnected-(SW16-P1-Pad3)") (class "Default")
      (node (ref "SW16") (pin "3") (pinfunction "P1_3") (pintype "passive"))
    )
    (net (code "118") (name "unconnected-(SW16-S1-Pad4)") (class "Default")
      (node (ref "SW16") (pin "4") (pinfunction "S1_4") (pintype "passive"))
    )
  )
)
